# design.net
KiCad netlist of a schematic drawn in Altium Designer
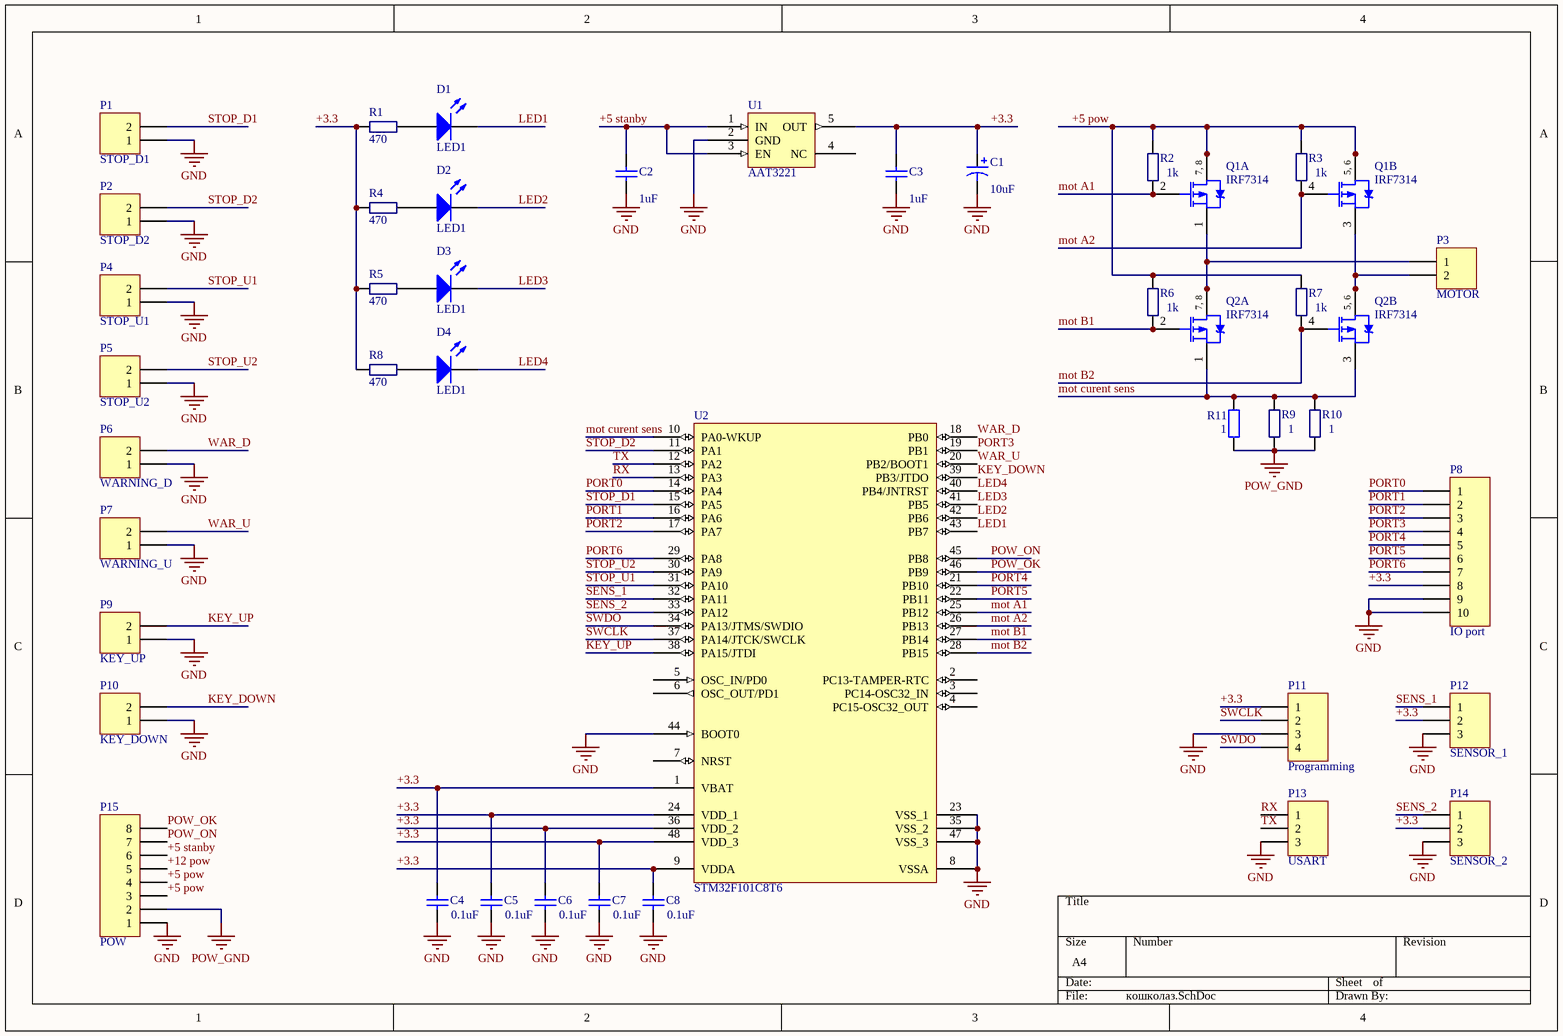
[diagram p0: кошколаз.SchDoc]

(export (version "E")
  (design (tool "Eeschema 10.0.6"))
  (components
    (comp (ref "C1")
      (value "10uF")
      (footprint "C0805")
      (description "Polarized Capacitor (Surface Mount)")
      (fields (field (name "PUBLISHER") "Altium Limited"))
      (libsource (lib "Miscellaneous Devices") (part "Cap Pol3"))
    )
    (comp (ref "C2")
      (value "1uF")
      (footprint "1608[0603]")
      (description "Capacitor (Semiconductor SIM Model)")
      (fields (field (name "PUBLISHER") "Altium Limited"))
      (libsource (lib "Miscellaneous Devices") (part "Cap Semi"))
    )
    (comp (ref "C3")
      (value "1uF")
      (footprint "1608[0603]")
      (description "Capacitor (Semiconductor SIM Model)")
      (fields (field (name "PUBLISHER") "Altium Limited"))
      (libsource (lib "Miscellaneous Devices") (part "Cap Semi"))
    )
    (comp (ref "C4")
      (value "0.1uF")
      (footprint "1608[0603]")
      (description "Capacitor (Semiconductor SIM Model)")
      (fields (field (name "PUBLISHER") "Altium Limited"))
      (libsource (lib "Miscellaneous Devices") (part "Cap Semi"))
    )
    (comp (ref "C5")
      (value "0.1uF")
      (footprint "1608[0603]")
      (description "Capacitor (Semiconductor SIM Model)")
      (fields (field (name "PUBLISHER") "Altium Limited"))
      (libsource (lib "Miscellaneous Devices") (part "Cap Semi"))
    )
    (comp (ref "C6")
      (value "0.1uF")
      (footprint "1608[0603]")
      (description "Capacitor (Semiconductor SIM Model)")
      (fields (field (name "PUBLISHER") "Altium Limited"))
      (libsource (lib "Miscellaneous Devices") (part "Cap Semi"))
    )
    (comp (ref "C7")
      (value "0.1uF")
      (footprint "1608[0603]")
      (description "Capacitor (Semiconductor SIM Model)")
      (fields (field (name "PUBLISHER") "Altium Limited"))
      (libsource (lib "Miscellaneous Devices") (part "Cap Semi"))
    )
    (comp (ref "C8")
      (value "0.1uF")
      (footprint "1608[0603]")
      (description "Capacitor (Semiconductor SIM Model)")
      (fields (field (name "PUBLISHER") "Altium Limited"))
      (libsource (lib "Miscellaneous Devices") (part "Cap Semi"))
    )
    (comp (ref "D1")
      (value "LED1")
      (footprint "LED-1")
      (description "Typical RED GaAs LED")
      (fields (field (name "PUBLISHER") "Altium Limited"))
      (libsource (lib "Miscellaneous Devices") (part "LED1"))
    )
    (comp (ref "D2")
      (value "LED1")
      (footprint "LED-1")
      (description "Typical RED GaAs LED")
      (fields (field (name "PUBLISHER") "Altium Limited"))
      (libsource (lib "Miscellaneous Devices") (part "LED1"))
    )
    (comp (ref "D3")
      (value "LED1")
      (footprint "LED-1")
      (description "Typical RED GaAs LED")
      (fields (field (name "PUBLISHER") "Altium Limited"))
      (libsource (lib "Miscellaneous Devices") (part "LED1"))
    )
    (comp (ref "D4")
      (value "LED1")
      (footprint "LED-1")
      (description "Typical RED GaAs LED")
      (fields (field (name "PUBLISHER") "Altium Limited"))
      (libsource (lib "Miscellaneous Devices") (part "LED1"))
    )
    (comp (ref "P1")
      (value "STOP_D1")
      (footprint "HDR1X2")
      (description "Header, 2-Pin")
      (fields (field (name "PUBLISHER") "Altium Limited"))
      (libsource (lib "Miscellaneous Connectors") (part "Header 2"))
    )
    (comp (ref "P2")
      (value "STOP_D2")
      (footprint "HDR1X2")
      (description "Header, 2-Pin")
      (fields (field (name "PUBLISHER") "Altium Limited"))
      (libsource (lib "Miscellaneous Connectors") (part "Header 2"))
    )
    (comp (ref "P3")
      (value "MOTOR")
      (footprint "HDR1X2")
      (description "Header, 2-Pin")
      (fields (field (name "PUBLISHER") "Altium Limited"))
      (libsource (lib "") (part "Header 2_1"))
    )
    (comp (ref "P4")
      (value "STOP_U1")
      (footprint "HDR1X2")
      (description "Header, 2-Pin")
      (fields (field (name "PUBLISHER") "Altium Limited"))
      (libsource (lib "Miscellaneous Connectors") (part "Header 2"))
    )
    (comp (ref "P5")
      (value "STOP_U2")
      (footprint "HDR1X2")
      (description "Header, 2-Pin")
      (fields (field (name "PUBLISHER") "Altium Limited"))
      (libsource (lib "Miscellaneous Connectors") (part "Header 2"))
    )
    (comp (ref "P6")
      (value "WARNING_D")
      (footprint "HDR1X2")
      (description "Header, 2-Pin")
      (fields (field (name "PUBLISHER") "Altium Limited"))
      (libsource (lib "Miscellaneous Connectors") (part "Header 2"))
    )
    (comp (ref "P7")
      (value "WARNING_U")
      (footprint "HDR1X2")
      (description "Header, 2-Pin")
      (fields (field (name "PUBLISHER") "Altium Limited"))
      (libsource (lib "Miscellaneous Connectors") (part "Header 2"))
    )
    (comp (ref "P8")
      (value "IO port")
      (footprint "HDR1X10")
      (description "Header, 10-Pin")
      (fields (field (name "PUBLISHER") "Altium Limited"))
      (libsource (lib "Miscellaneous Connectors") (part "Header 10"))
    )
    (comp (ref "P9")
      (value "KEY_UP")
      (footprint "HDR1X2")
      (description "Header, 2-Pin")
      (fields (field (name "PUBLISHER") "Altium Limited"))
      (libsource (lib "Miscellaneous Connectors") (part "Header 2"))
    )
    (comp (ref "P10")
      (value "KEY_DOWN")
      (footprint "HDR1X2")
      (description "Header, 2-Pin")
      (fields (field (name "PUBLISHER") "Altium Limited"))
      (libsource (lib "Miscellaneous Connectors") (part "Header 2"))
    )
    (comp (ref "P11")
      (value "Programming")
      (footprint "HDR1X4")
      (description "Header, 4-Pin")
      (fields (field (name "PUBLISHER") "Altium Limited"))
      (libsource (lib "Miscellaneous Connectors") (part "Header 4"))
    )
    (comp (ref "P12")
      (value "SENSOR_1")
      (footprint "HDR1X3")
      (description "Header, 3-Pin")
      (fields (field (name "PUBLISHER") "Altium Limited"))
      (libsource (lib "Miscellaneous Connectors") (part "Header 3"))
    )
    (comp (ref "P13")
      (value "USART")
      (footprint "HDR1X3")
      (description "Header, 3-Pin")
      (fields (field (name "PUBLISHER") "Altium Limited"))
      (libsource (lib "Miscellaneous Connectors") (part "Header 3"))
    )
    (comp (ref "P14")
      (value "SENSOR_2")
      (footprint "HDR1X3")
      (description "Header, 3-Pin")
      (fields (field (name "PUBLISHER") "Altium Limited"))
      (libsource (lib "Miscellaneous Connectors") (part "Header 3"))
    )
    (comp (ref "P15")
      (value "POW")
      (footprint "HDR1X8")
      (description "Header, 8-Pin")
      (fields (field (name "PUBLISHER") "Altium Limited"))
      (libsource (lib "Miscellaneous Connectors") (part "Header 8"))
    )
    (comp (ref "Q1")
      (value "IRF7314")
      (footprint "SO-8_N")
      (description "HEXFET Power MOSFET")
      (fields (field (name "PUBLISHER") "Altium Limited"))
      (libsource (lib "IR Discrete MOSFET - Power") (part "IRF7314"))
    )
    (comp (ref "Q2")
      (value "IRF7314")
      (footprint "SO-8_N")
      (description "HEXFET Power MOSFET")
      (fields (field (name "PUBLISHER") "Altium Limited"))
      (libsource (lib "IR Discrete MOSFET - Power") (part "IRF7314"))
    )
    (comp (ref "R1")
      (value "470")
      (footprint "J1-0603")
      (description "Resistor")
      (fields (field (name "PUBLISHER") "Altium Limited"))
      (libsource (lib "LockLib") (part "Res_SMD"))
    )
    (comp (ref "R2")
      (value "1k")
      (footprint "J1-0603")
      (description "Resistor")
      (fields (field (name "PUBLISHER") "Altium Limited"))
      (libsource (lib "LockLib") (part "Res_SMD"))
    )
    (comp (ref "R3")
      (value "1k")
      (footprint "J1-0603")
      (description "Resistor")
      (fields (field (name "PUBLISHER") "Altium Limited"))
      (libsource (lib "LockLib") (part "Res_SMD"))
    )
    (comp (ref "R4")
      (value "470")
      (footprint "J1-0603")
      (description "Resistor")
      (fields (field (name "PUBLISHER") "Altium Limited"))
      (libsource (lib "LockLib") (part "Res_SMD"))
    )
    (comp (ref "R5")
      (value "470")
      (footprint "J1-0603")
      (description "Resistor")
      (fields (field (name "PUBLISHER") "Altium Limited"))
      (libsource (lib "LockLib") (part "Res_SMD"))
    )
    (comp (ref "R6")
      (value "1k")
      (footprint "J1-0603")
      (description "Resistor")
      (fields (field (name "PUBLISHER") "Altium Limited"))
      (libsource (lib "LockLib") (part "Res_SMD"))
    )
    (comp (ref "R7")
      (value "1k")
      (footprint "J1-0603")
      (description "Resistor")
      (fields (field (name "PUBLISHER") "Altium Limited"))
      (libsource (lib "LockLib") (part "Res_SMD"))
    )
    (comp (ref "R8")
      (value "470")
      (footprint "J1-0603")
      (description "Resistor")
      (fields (field (name "PUBLISHER") "Altium Limited"))
      (libsource (lib "LockLib") (part "Res_SMD"))
    )
    (comp (ref "R9")
      (value "1")
      (footprint "6-0805_N")
      (description "Resistor")
      (fields (field (name "PUBLISHER") "Altium Limited"))
      (libsource (lib "LockLib") (part "Res_SMD"))
    )
    (comp (ref "R10")
      (value "1")
      (footprint "6-0805_N")
      (description "Resistor")
      (fields (field (name "PUBLISHER") "Altium Limited"))
      (libsource (lib "LockLib") (part "Res_SMD"))
    )
    (comp (ref "R11")
      (value "1")
      (footprint "AXIAL-0.4")
      (description "Resistor")
      (fields (field (name "PUBLISHER") "Altium Limited"))
      (libsource (lib "Miscellaneous Devices") (part "Res2"))
    )
    (comp (ref "U1")
      (value "AAT3221")
      (footprint "SOT23-5")
      (description "Low Dropout Linear Regulator")
      (libsource (lib "LockLib") (part "AAT3221"))
    )
    (comp (ref "U2")
      (value "STM32F101C8T6")
      (footprint "LQFP48_M")
      (description "STM32 ARM-based 32-bit MCU with 64 Kbytes Flash, 48-pin LQFP, Industrial Temperature")
      (fields (field (name "PUBLISHER") "Altium Limited"))
      (libsource (lib "ST Microcontroller 32-Bit STM32") (part "STM32F101C8T6"))
    )
  )
  (nets
    (net (code "1") (name "/+3.3") (class "Default")
      (node (ref "C1") (pin "1") (pinfunction "1_1") (pintype "passive"))
      (node (ref "C3") (pin "2") (pinfunction "2_2") (pintype "passive"))
      (node (ref "C4") (pin "2") (pinfunction "2_2") (pintype "passive"))
      (node (ref "C5") (pin "2") (pinfunction "2_2") (pintype "passive"))
      (node (ref "C6") (pin "2") (pinfunction "2_2") (pintype "passive"))
      (node (ref "C7") (pin "2") (pinfunction "2_2") (pintype "passive"))
      (node (ref "C8") (pin "2") (pinfunction "2_2") (pintype "passive"))
      (node (ref "P11") (pin "1") (pinfunction "1_1") (pintype "passive"))
      (node (ref "P12") (pin "2") (pinfunction "2_2") (pintype "passive"))
      (node (ref "P14") (pin "2") (pinfunction "2_2") (pintype "passive"))
      (node (ref "P8") (pin "8") (pinfunction "8_8") (pintype "passive"))
      (node (ref "R1") (pin "2") (pinfunction "2_2") (pintype "passive"))
      (node (ref "R4") (pin "2") (pinfunction "2_2") (pintype "passive"))
      (node (ref "R5") (pin "2") (pinfunction "2_2") (pintype "passive"))
      (node (ref "R8") (pin "2") (pinfunction "2_2") (pintype "passive"))
      (node (ref "U1") (pin "5") (pinfunction "OUT_5") (pintype "output"))
      (node (ref "U2") (pin "1") (pinfunction "VBAT_1") (pintype "power_in"))
      (node (ref "U2") (pin "24") (pinfunction "VDD_1_24") (pintype "power_in"))
      (node (ref "U2") (pin "36") (pinfunction "VDD_2_36") (pintype "power_in"))
      (node (ref "U2") (pin "48") (pinfunction "VDD_3_48") (pintype "power_in"))
      (node (ref "U2") (pin "9") (pinfunction "VDDA_9") (pintype "power_in"))
    )
    (net (code "2") (name "/+5 pow") (class "Default")
      (node (ref "P15") (pin "3") (pinfunction "3_3") (pintype "passive"))
      (node (ref "P15") (pin "4") (pinfunction "4_4") (pintype "passive"))
      (node (ref "Q1") (pin "5") (pinfunction "D_5") (pintype "passive"))
      (node (ref "Q1") (pin "6") (pinfunction "D_6") (pintype "passive"))
      (node (ref "Q1") (pin "7") (pinfunction "D_7") (pintype "passive"))
      (node (ref "Q1") (pin "8") (pinfunction "D_8") (pintype "passive"))
      (node (ref "R2") (pin "2") (pinfunction "2_2") (pintype "passive"))
      (node (ref "R3") (pin "2") (pinfunction "2_2") (pintype "passive"))
      (node (ref "R6") (pin "2") (pinfunction "2_2") (pintype "passive"))
      (node (ref "R7") (pin "2") (pinfunction "2_2") (pintype "passive"))
    )
    (net (code "3") (name "/+5 stanby") (class "Default")
      (node (ref "C2") (pin "2") (pinfunction "2_2") (pintype "passive"))
      (node (ref "P15") (pin "6") (pinfunction "6_6") (pintype "passive"))
      (node (ref "U1") (pin "1") (pinfunction "IN_1") (pintype "input"))
      (node (ref "U1") (pin "3") (pinfunction "EN_3") (pintype "input"))
    )
    (net (code "4") (name "/+12 pow") (class "Default")
      (node (ref "P15") (pin "5") (pinfunction "5_5") (pintype "passive"))
    )
    (net (code "5") (name "/KEY_DOWN") (class "Default")
      (node (ref "P10") (pin "2") (pinfunction "2_2") (pintype "passive"))
      (node (ref "U2") (pin "39") (pinfunction "PB3/JTDO_39") (pintype "bidirectional"))
    )
    (net (code "6") (name "/KEY_UP") (class "Default")
      (node (ref "P9") (pin "2") (pinfunction "2_2") (pintype "passive"))
      (node (ref "U2") (pin "38") (pinfunction "PA15/JTDI_38") (pintype "bidirectional"))
    )
    (net (code "7") (name "/LED1") (class "Default")
      (node (ref "D1") (pin "2") (pinfunction "K_2") (pintype "passive"))
      (node (ref "U2") (pin "43") (pinfunction "PB7_43") (pintype "bidirectional"))
    )
    (net (code "8") (name "/LED2") (class "Default")
      (node (ref "D2") (pin "2") (pinfunction "K_2") (pintype "passive"))
      (node (ref "U2") (pin "42") (pinfunction "PB6_42") (pintype "bidirectional"))
    )
    (net (code "9") (name "/LED3") (class "Default")
      (node (ref "D3") (pin "2") (pinfunction "K_2") (pintype "passive"))
      (node (ref "U2") (pin "41") (pinfunction "PB5_41") (pintype "bidirectional"))
    )
    (net (code "10") (name "/LED4") (class "Default")
      (node (ref "D4") (pin "2") (pinfunction "K_2") (pintype "passive"))
      (node (ref "U2") (pin "40") (pinfunction "PB4/JNTRST_40") (pintype "bidirectional"))
    )
    (net (code "11") (name "/PORT0") (class "Default")
      (node (ref "P8") (pin "1") (pinfunction "1_1") (pintype "passive"))
      (node (ref "U2") (pin "14") (pinfunction "PA4_14") (pintype "bidirectional"))
    )
    (net (code "12") (name "/PORT1") (class "Default")
      (node (ref "P8") (pin "2") (pinfunction "2_2") (pintype "passive"))
      (node (ref "U2") (pin "16") (pinfunction "PA6_16") (pintype "bidirectional"))
    )
    (net (code "13") (name "/PORT2") (class "Default")
      (node (ref "P8") (pin "3") (pinfunction "3_3") (pintype "passive"))
      (node (ref "U2") (pin "17") (pinfunction "PA7_17") (pintype "bidirectional"))
    )
    (net (code "14") (name "/PORT3") (class "Default")
      (node (ref "P8") (pin "4") (pinfunction "4_4") (pintype "passive"))
      (node (ref "U2") (pin "19") (pinfunction "PB1_19") (pintype "bidirectional"))
    )
    (net (code "15") (name "/PORT4") (class "Default")
      (node (ref "P8") (pin "5") (pinfunction "5_5") (pintype "passive"))
      (node (ref "U2") (pin "21") (pinfunction "PB10_21") (pintype "bidirectional"))
    )
    (net (code "16") (name "/PORT5") (class "Default")
      (node (ref "P8") (pin "6") (pinfunction "6_6") (pintype "passive"))
      (node (ref "U2") (pin "22") (pinfunction "PB11_22") (pintype "bidirectional"))
    )
    (net (code "17") (name "/PORT6") (class "Default")
      (node (ref "P8") (pin "7") (pinfunction "7_7") (pintype "passive"))
      (node (ref "U2") (pin "29") (pinfunction "PA8_29") (pintype "bidirectional"))
    )
    (net (code "18") (name "/POW_OK") (class "Default")
      (node (ref "P15") (pin "8") (pinfunction "8_8") (pintype "passive"))
      (node (ref "U2") (pin "46") (pinfunction "PB9_46") (pintype "bidirectional"))
    )
    (net (code "19") (name "/POW_ON") (class "Default")
      (node (ref "P15") (pin "7") (pinfunction "7_7") (pintype "passive"))
      (node (ref "U2") (pin "45") (pinfunction "PB8_45") (pintype "bidirectional"))
    )
    (net (code "20") (name "/RX") (class "Default")
      (node (ref "P13") (pin "1") (pinfunction "1_1") (pintype "passive"))
      (node (ref "U2") (pin "13") (pinfunction "PA3_13") (pintype "bidirectional"))
    )
    (net (code "21") (name "/SENS_1") (class "Default")
      (node (ref "P12") (pin "1") (pinfunction "1_1") (pintype "passive"))
      (node (ref "U2") (pin "32") (pinfunction "PA11_32") (pintype "bidirectional"))
    )
    (net (code "22") (name "/SENS_2") (class "Default")
      (node (ref "P14") (pin "1") (pinfunction "1_1") (pintype "passive"))
      (node (ref "U2") (pin "33") (pinfunction "PA12_33") (pintype "bidirectional"))
    )
    (net (code "23") (name "/STOP_D1") (class "Default")
      (node (ref "P1") (pin "2") (pinfunction "2_2") (pintype "passive"))
      (node (ref "U2") (pin "15") (pinfunction "PA5_15") (pintype "bidirectional"))
    )
    (net (code "24") (name "/STOP_D2") (class "Default")
      (node (ref "P2") (pin "2") (pinfunction "2_2") (pintype "passive"))
      (node (ref "U2") (pin "11") (pinfunction "PA1_11") (pintype "bidirectional"))
    )
    (net (code "25") (name "/STOP_U1") (class "Default")
      (node (ref "P4") (pin "2") (pinfunction "2_2") (pintype "passive"))
      (node (ref "U2") (pin "31") (pinfunction "PA10_31") (pintype "bidirectional"))
    )
    (net (code "26") (name "/STOP_U2") (class "Default")
      (node (ref "P5") (pin "2") (pinfunction "2_2") (pintype "passive"))
      (node (ref "U2") (pin "30") (pinfunction "PA9_30") (pintype "bidirectional"))
    )
    (net (code "27") (name "/SWCLK") (class "Default")
      (node (ref "P11") (pin "2") (pinfunction "2_2") (pintype "passive"))
      (node (ref "U2") (pin "37") (pinfunction "PA14/JTCK/SWCLK_37") (pintype "bidirectional"))
    )
    (net (code "28") (name "/SWDO") (class "Default")
      (node (ref "P11") (pin "4") (pinfunction "4_4") (pintype "passive"))
      (node (ref "U2") (pin "34") (pinfunction "PA13/JTMS/SWDIO_34") (pintype "bidirectional"))
    )
    (net (code "29") (name "/TX") (class "Default")
      (node (ref "P13") (pin "2") (pinfunction "2_2") (pintype "passive"))
      (node (ref "U2") (pin "12") (pinfunction "PA2_12") (pintype "bidirectional"))
    )
    (net (code "30") (name "/WAR_D") (class "Default")
      (node (ref "P6") (pin "2") (pinfunction "2_2") (pintype "passive"))
      (node (ref "U2") (pin "18") (pinfunction "PB0_18") (pintype "bidirectional"))
    )
    (net (code "31") (name "/WAR_U") (class "Default")
      (node (ref "P7") (pin "2") (pinfunction "2_2") (pintype "passive"))
      (node (ref "U2") (pin "20") (pinfunction "PB2/BOOT1_20") (pintype "bidirectional"))
    )
    (net (code "32") (name "/mot A1") (class "Default")
      (node (ref "Q1") (pin "2") (pinfunction "G_2") (pintype "passive"))
      (node (ref "R2") (pin "1") (pinfunction "1_1") (pintype "passive"))
      (node (ref "U2") (pin "25") (pinfunction "PB12_25") (pintype "bidirectional"))
    )
    (net (code "33") (name "/mot A2") (class "Default")
      (node (ref "Q1") (pin "4") (pinfunction "G_4") (pintype "passive"))
      (node (ref "R3") (pin "1") (pinfunction "1_1") (pintype "passive"))
      (node (ref "U2") (pin "26") (pinfunction "PB13_26") (pintype "bidirectional"))
    )
    (net (code "34") (name "/mot B1") (class "Default")
      (node (ref "Q2") (pin "2") (pinfunction "G_2") (pintype "passive"))
      (node (ref "R6") (pin "1") (pinfunction "1_1") (pintype "passive"))
      (node (ref "U2") (pin "27") (pinfunction "PB14_27") (pintype "bidirectional"))
    )
    (net (code "35") (name "/mot B2") (class "Default")
      (node (ref "Q2") (pin "4") (pinfunction "G_4") (pintype "passive"))
      (node (ref "R7") (pin "1") (pinfunction "1_1") (pintype "passive"))
      (node (ref "U2") (pin "28") (pinfunction "PB15_28") (pintype "bidirectional"))
    )
    (net (code "36") (name "/mot curent sens") (class "Default")
      (node (ref "Q2") (pin "1") (pinfunction "S_1") (pintype "passive"))
      (node (ref "Q2") (pin "3") (pinfunction "S_3") (pintype "passive"))
      (node (ref "R10") (pin "2") (pinfunction "2_2") (pintype "passive"))
      (node (ref "R11") (pin "2") (pinfunction "2_2") (pintype "passive"))
      (node (ref "R9") (pin "2") (pinfunction "2_2") (pintype "passive"))
      (node (ref "U2") (pin "10") (pinfunction "PA0-WKUP_10") (pintype "bidirectional"))
    )
    (net (code "37") (name "GND") (class "Default")
      (node (ref "C1") (pin "2") (pinfunction "2_2") (pintype "passive"))
      (node (ref "C2") (pin "1") (pinfunction "1_1") (pintype "passive"))
      (node (ref "C3") (pin "1") (pinfunction "1_1") (pintype "passive"))
      (node (ref "C4") (pin "1") (pinfunction "1_1") (pintype "passive"))
      (node (ref "C5") (pin "1") (pinfunction "1_1") (pintype "passive"))
      (node (ref "C6") (pin "1") (pinfunction "1_1") (pintype "passive"))
      (node (ref "C7") (pin "1") (pinfunction "1_1") (pintype "passive"))
      (node (ref "C8") (pin "1") (pinfunction "1_1") (pintype "passive"))
      (node (ref "P1") (pin "1") (pinfunction "1_1") (pintype "passive"))
      (node (ref "P10") (pin "1") (pinfunction "1_1") (pintype "passive"))
      (node (ref "P11") (pin "3") (pinfunction "3_3") (pintype "passive"))
      (node (ref "P12") (pin "3") (pinfunction "3_3") (pintype "passive"))
      (node (ref "P13") (pin "3") (pinfunction "3_3") (pintype "passive"))
      (node (ref "P14") (pin "3") (pinfunction "3_3") (pintype "passive"))
      (node (ref "P15") (pin "1") (pinfunction "1_1") (pintype "passive"))
      (node (ref "P2") (pin "1") (pinfunction "1_1") (pintype "passive"))
      (node (ref "P4") (pin "1") (pinfunction "1_1") (pintype "passive"))
      (node (ref "P5") (pin "1") (pinfunction "1_1") (pintype "passive"))
      (node (ref "P6") (pin "1") (pinfunction "1_1") (pintype "passive"))
      (node (ref "P7") (pin "1") (pinfunction "1_1") (pintype "passive"))
      (node (ref "P8") (pin "10") (pinfunction "10_10") (pintype "passive"))
      (node (ref "P8") (pin "9") (pinfunction "9_9") (pintype "passive"))
      (node (ref "P9") (pin "1") (pinfunction "1_1") (pintype "passive"))
      (node (ref "U1") (pin "2") (pinfunction "GND_2") (pintype "power_in"))
      (node (ref "U2") (pin "23") (pinfunction "VSS_1_23") (pintype "power_in"))
      (node (ref "U2") (pin "35") (pinfunction "VSS_2_35") (pintype "power_in"))
      (node (ref "U2") (pin "44") (pinfunction "BOOT0_44") (pintype "input"))
      (node (ref "U2") (pin "47") (pinfunction "VSS_3_47") (pintype "power_in"))
      (node (ref "U2") (pin "8") (pinfunction "VSSA_8") (pintype "power_in"))
    )
    (net (code "38") (name "Net-(D1-A)") (class "Default")
      (node (ref "D1") (pin "1") (pinfunction "A_1") (pintype "passive"))
      (node (ref "R1") (pin "1") (pinfunction "1_1") (pintype "passive"))
    )
    (net (code "39") (name "Net-(D2-A)") (class "Default")
      (node (ref "D2") (pin "1") (pinfunction "A_1") (pintype "passive"))
      (node (ref "R4") (pin "1") (pinfunction "1_1") (pintype "passive"))
    )
    (net (code "40") (name "Net-(D3-A)") (class "Default")
      (node (ref "D3") (pin "1") (pinfunction "A_1") (pintype "passive"))
      (node (ref "R5") (pin "1") (pinfunction "1_1") (pintype "passive"))
    )
    (net (code "41") (name "Net-(D4-A)") (class "Default")
      (node (ref "D4") (pin "1") (pinfunction "A_1") (pintype "passive"))
      (node (ref "R8") (pin "1") (pinfunction "1_1") (pintype "passive"))
    )
    (net (code "42") (name "Net-(Q1A-S)") (class "Default")
      (node (ref "P3") (pin "1") (pinfunction "1_1") (pintype "passive"))
      (node (ref "Q1") (pin "1") (pinfunction "S_1") (pintype "passive"))
      (node (ref "Q2") (pin "7") (pinfunction "D_7") (pintype "passive"))
      (node (ref "Q2") (pin "8") (pinfunction "D_8") (pintype "passive"))
    )
    (net (code "43") (name "Net-(Q1B-S)") (class "Default")
      (node (ref "P3") (pin "2") (pinfunction "2_2") (pintype "passive"))
      (node (ref "Q1") (pin "3") (pinfunction "S_3") (pintype "passive"))
      (node (ref "Q2") (pin "5") (pinfunction "D_5") (pintype "passive"))
      (node (ref "Q2") (pin "6") (pinfunction "D_6") (pintype "passive"))
    )
    (net (code "44") (name "POW_GND") (class "Default")
      (node (ref "P15") (pin "2") (pinfunction "2_2") (pintype "passive"))
      (node (ref "R10") (pin "1") (pinfunction "1_1") (pintype "passive"))
      (node (ref "R11") (pin "1") (pinfunction "1_1") (pintype "passive"))
      (node (ref "R9") (pin "1") (pinfunction "1_1") (pintype "passive"))
    )
    (net (code "45") (name "unconnected-(U1-NC-Pad4)") (class "Default")
      (node (ref "U1") (pin "4") (pinfunction "NC_4") (pintype "passive"))
    )
    (net (code "46") (name "unconnected-(U2-NRST-Pad7)") (class "Default")
      (node (ref "U2") (pin "7") (pinfunction "NRST_7") (pintype "bidirectional"))
    )
    (net (code "47") (name "unconnected-(U2-OSC_IN{slash}PD0-Pad5)") (class "Default")
      (node (ref "U2") (pin "5") (pinfunction "OSC_IN/PD0_5") (pintype "input"))
    )
    (net (code "48") (name "unconnected-(U2-OSC_OUT{slash}PD1-Pad6)") (class "Default")
      (node (ref "U2") (pin "6") (pinfunction "OSC_OUT/PD1_6") (pintype "output"))
    )
    (net (code "49") (name "unconnected-(U2-PC13-TAMPER-RTC-Pad2)") (class "Default")
      (node (ref "U2") (pin "2") (pinfunction "PC13-TAMPER-RTC_2") (pintype "bidirectional"))
    )
    (net (code "50") (name "unconnected-(U2-PC14-OSC32_IN-Pad3)") (class "Default")
      (node (ref "U2") (pin "3") (pinfunction "PC14-OSC32_IN_3") (pintype "bidirectional"))
    )
    (net (code "51") (name "unconnected-(U2-PC15-OSC32_OUT-Pad4)") (class "Default")
      (node (ref "U2") (pin "4") (pinfunction "PC15-OSC32_OUT_4") (pintype "bidirectional"))
    )
  )
)
